# Esquema.net
KiCad netlist of a schematic drawn in EAGLE
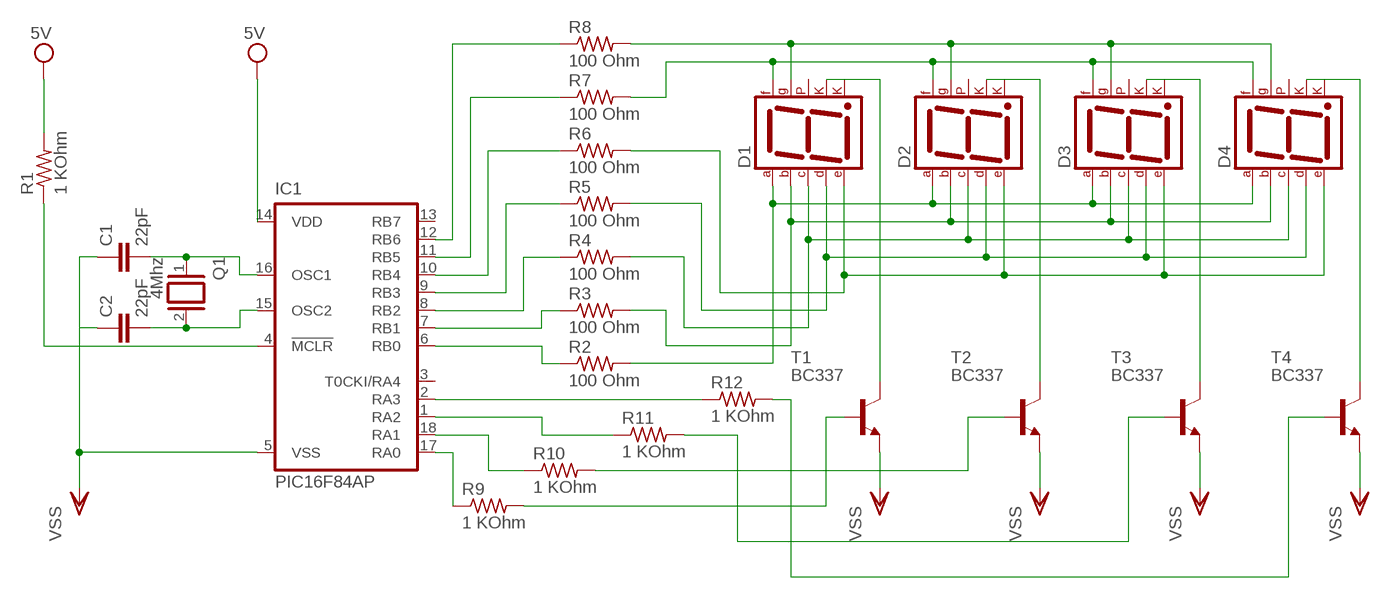
[diagram p0: schematic, sheet 1]

(export (version "E")
  (design (tool "Eeschema 10.0.6"))
  (components
    (comp (ref "C1")
      (value "22pF")
      (footprint "eagle-import:C2.5-4")
      (libsource (lib "eagle-import") (part "C2.5/4"))
    )
    (comp (ref "C2")
      (value "22pF")
      (footprint "eagle-import:C2.5-4")
      (libsource (lib "eagle-import") (part "C2.5/4"))
    )
    (comp (ref "D1")
      (value "7SEG-CK")
      (footprint "eagle-import:7SEG-13")
      (libsource (lib "eagle-import") (part "7SEG-CK"))
    )
    (comp (ref "D2")
      (value "7SEG-CK")
      (footprint "eagle-import:7SEG-13")
      (libsource (lib "eagle-import") (part "7SEG-CK"))
    )
    (comp (ref "D3")
      (value "7SEG-CK")
      (footprint "eagle-import:7SEG-13")
      (libsource (lib "eagle-import") (part "7SEG-CK"))
    )
    (comp (ref "D4")
      (value "7SEG-CK")
      (footprint "eagle-import:7SEG-13")
      (libsource (lib "eagle-import") (part "7SEG-CK"))
    )
    (comp (ref "IC1")
      (value "PIC16F84AP")
      (footprint "eagle-import:DIL18")
      (fields (field (name "MF") "MICROCHIP") (field (name "MPN") "PIC16F84A-04I/P"))
      (libsource (lib "eagle-import") (part "PIC16F8P4A"))
    )
    (comp (ref "Q1")
      (value "4Mhz")
      (footprint "eagle-import:Q")
      (libsource (lib "eagle-import") (part "XTAL"))
    )
    (comp (ref "R1")
      (value "1 KOhm")
      (footprint "eagle-import:0204_5")
      (libsource (lib "eagle-import") (part "R-US_0204/5"))
    )
    (comp (ref "R2")
      (value "100 Ohm")
      (footprint "eagle-import:0204_5")
      (libsource (lib "eagle-import") (part "R-US_0204/5"))
    )
    (comp (ref "R3")
      (value "100 Ohm")
      (footprint "eagle-import:0204_5")
      (libsource (lib "eagle-import") (part "R-US_0204/5"))
    )
    (comp (ref "R4")
      (value "100 Ohm")
      (footprint "eagle-import:0204_5")
      (libsource (lib "eagle-import") (part "R-US_0204/5"))
    )
    (comp (ref "R5")
      (value "100 Ohm")
      (footprint "eagle-import:0204_5")
      (libsource (lib "eagle-import") (part "R-US_0204/5"))
    )
    (comp (ref "R6")
      (value "100 Ohm")
      (footprint "eagle-import:0204_5")
      (libsource (lib "eagle-import") (part "R-US_0204/5"))
    )
    (comp (ref "R7")
      (value "100 Ohm")
      (footprint "eagle-import:0204_5")
      (libsource (lib "eagle-import") (part "R-US_0204/5"))
    )
    (comp (ref "R8")
      (value "100 Ohm")
      (footprint "eagle-import:0204_5")
      (libsource (lib "eagle-import") (part "R-US_0204/5"))
    )
    (comp (ref "R9")
      (value "1 KOhm")
      (footprint "eagle-import:0204_5")
      (libsource (lib "eagle-import") (part "R-US_0204/5"))
    )
    (comp (ref "R10")
      (value "1 KOhm")
      (footprint "eagle-import:0204_5")
      (libsource (lib "eagle-import") (part "R-US_0204/5"))
    )
    (comp (ref "R11")
      (value "1 KOhm")
      (footprint "eagle-import:0204_5")
      (libsource (lib "eagle-import") (part "R-US_0204/5"))
    )
    (comp (ref "R12")
      (value "1 KOhm")
      (footprint "eagle-import:0204_5")
      (libsource (lib "eagle-import") (part "R-US_0204/5"))
    )
    (comp (ref "T1")
      (value "BC337")
      (footprint "eagle-import:TO92")
      (libsource (lib "eagle-import") (part "BC337"))
    )
    (comp (ref "T2")
      (value "BC337")
      (footprint "eagle-import:TO92")
      (libsource (lib "eagle-import") (part "BC337"))
    )
    (comp (ref "T3")
      (value "BC337")
      (footprint "eagle-import:TO92")
      (libsource (lib "eagle-import") (part "BC337"))
    )
    (comp (ref "T4")
      (value "BC337")
      (footprint "eagle-import:TO92")
      (libsource (lib "eagle-import") (part "BC337"))
    )
  )
  (nets
    (net (code "1") (name "5V") (class "Default")
      (node (ref "IC1") (pin "14") (pinfunction "VDD_14") (pintype "power_in"))
      (node (ref "R1") (pin "2") (pinfunction "2_2") (pintype "passive"))
    )
    (net (code "2") (name "Net-(D1-A)") (class "Default")
      (node (ref "D1") (pin "7") (pinfunction "A_7") (pintype "passive"))
      (node (ref "D2") (pin "7") (pinfunction "A_7") (pintype "passive"))
      (node (ref "D3") (pin "7") (pinfunction "A_7") (pintype "passive"))
      (node (ref "D4") (pin "7") (pinfunction "A_7") (pintype "passive"))
      (node (ref "R2") (pin "2") (pinfunction "2_2") (pintype "passive"))
    )
    (net (code "3") (name "Net-(D1-B)") (class "Default")
      (node (ref "D1") (pin "6") (pinfunction "B_6") (pintype "passive"))
      (node (ref "D2") (pin "6") (pinfunction "B_6") (pintype "passive"))
      (node (ref "D3") (pin "6") (pinfunction "B_6") (pintype "passive"))
      (node (ref "D4") (pin "6") (pinfunction "B_6") (pintype "passive"))
      (node (ref "R3") (pin "2") (pinfunction "2_2") (pintype "passive"))
    )
    (net (code "4") (name "Net-(D1-C)") (class "Default")
      (node (ref "D1") (pin "4") (pinfunction "C_4") (pintype "passive"))
      (node (ref "D2") (pin "4") (pinfunction "C_4") (pintype "passive"))
      (node (ref "D3") (pin "4") (pinfunction "C_4") (pintype "passive"))
      (node (ref "D4") (pin "4") (pinfunction "C_4") (pintype "passive"))
      (node (ref "R4") (pin "2") (pinfunction "2_2") (pintype "passive"))
    )
    (net (code "5") (name "Net-(D1-CK1)") (class "Default")
      (node (ref "D1") (pin "3") (pinfunction "CK1_3") (pintype "passive"))
      (node (ref "D1") (pin "8") (pinfunction "CK2_8") (pintype "passive"))
      (node (ref "T1") (pin "3") (pinfunction "C_3") (pintype "passive"))
    )
    (net (code "6") (name "Net-(D1-D)") (class "Default")
      (node (ref "D1") (pin "2") (pinfunction "D_2") (pintype "passive"))
      (node (ref "D2") (pin "2") (pinfunction "D_2") (pintype "passive"))
      (node (ref "D3") (pin "2") (pinfunction "D_2") (pintype "passive"))
      (node (ref "D4") (pin "2") (pinfunction "D_2") (pintype "passive"))
      (node (ref "R5") (pin "2") (pinfunction "2_2") (pintype "passive"))
    )
    (net (code "7") (name "Net-(D1-E)") (class "Default")
      (node (ref "D1") (pin "1") (pinfunction "E_1") (pintype "passive"))
      (node (ref "D2") (pin "1") (pinfunction "E_1") (pintype "passive"))
      (node (ref "D3") (pin "1") (pinfunction "E_1") (pintype "passive"))
      (node (ref "D4") (pin "1") (pinfunction "E_1") (pintype "passive"))
      (node (ref "R6") (pin "2") (pinfunction "2_2") (pintype "passive"))
    )
    (net (code "8") (name "Net-(D1-F)") (class "Default")
      (node (ref "D1") (pin "9") (pinfunction "F_9") (pintype "passive"))
      (node (ref "D2") (pin "9") (pinfunction "F_9") (pintype "passive"))
      (node (ref "D3") (pin "9") (pinfunction "F_9") (pintype "passive"))
      (node (ref "D4") (pin "9") (pinfunction "F_9") (pintype "passive"))
      (node (ref "R7") (pin "2") (pinfunction "2_2") (pintype "passive"))
    )
    (net (code "9") (name "Net-(D1-G)") (class "Default")
      (node (ref "D1") (pin "10") (pinfunction "G_10") (pintype "passive"))
      (node (ref "D2") (pin "10") (pinfunction "G_10") (pintype "passive"))
      (node (ref "D3") (pin "10") (pinfunction "G_10") (pintype "passive"))
      (node (ref "D4") (pin "10") (pinfunction "G_10") (pintype "passive"))
      (node (ref "R8") (pin "2") (pinfunction "2_2") (pintype "passive"))
    )
    (net (code "10") (name "Net-(D2-CK1)") (class "Default")
      (node (ref "D2") (pin "3") (pinfunction "CK1_3") (pintype "passive"))
      (node (ref "D2") (pin "8") (pinfunction "CK2_8") (pintype "passive"))
      (node (ref "T2") (pin "3") (pinfunction "C_3") (pintype "passive"))
    )
    (net (code "11") (name "Net-(D3-CK1)") (class "Default")
      (node (ref "D3") (pin "3") (pinfunction "CK1_3") (pintype "passive"))
      (node (ref "D3") (pin "8") (pinfunction "CK2_8") (pintype "passive"))
      (node (ref "T3") (pin "3") (pinfunction "C_3") (pintype "passive"))
    )
    (net (code "12") (name "Net-(D4-CK1)") (class "Default")
      (node (ref "D4") (pin "3") (pinfunction "CK1_3") (pintype "passive"))
      (node (ref "D4") (pin "8") (pinfunction "CK2_8") (pintype "passive"))
      (node (ref "T4") (pin "3") (pinfunction "C_3") (pintype "passive"))
    )
    (net (code "13") (name "Net-(IC1-OSC1)") (class "Default")
      (node (ref "C1") (pin "2") (pinfunction "2_2") (pintype "passive"))
      (node (ref "IC1") (pin "16") (pinfunction "OSC1_16") (pintype "input"))
      (node (ref "Q1") (pin "1") (pinfunction "1_1") (pintype "passive"))
    )
    (net (code "14") (name "Net-(IC1-OSC2)") (class "Default")
      (node (ref "C2") (pin "2") (pinfunction "2_2") (pintype "passive"))
      (node (ref "IC1") (pin "15") (pinfunction "OSC2_15") (pintype "output"))
      (node (ref "Q1") (pin "2") (pinfunction "2_2") (pintype "passive"))
    )
    (net (code "15") (name "Net-(IC1-RA0)") (class "Default")
      (node (ref "IC1") (pin "17") (pinfunction "RA0_17") (pintype "bidirectional"))
      (node (ref "R9") (pin "1") (pinfunction "1_1") (pintype "passive"))
    )
    (net (code "16") (name "Net-(IC1-RA1)") (class "Default")
      (node (ref "IC1") (pin "18") (pinfunction "RA1_18") (pintype "bidirectional"))
      (node (ref "R10") (pin "1") (pinfunction "1_1") (pintype "passive"))
    )
    (net (code "17") (name "Net-(IC1-RA2)") (class "Default")
      (node (ref "IC1") (pin "1") (pinfunction "RA2_1") (pintype "bidirectional"))
      (node (ref "R11") (pin "1") (pinfunction "1_1") (pintype "passive"))
    )
    (net (code "18") (name "Net-(IC1-RA3)") (class "Default")
      (node (ref "IC1") (pin "2") (pinfunction "RA3_2") (pintype "bidirectional"))
      (node (ref "R12") (pin "1") (pinfunction "1_1") (pintype "passive"))
    )
    (net (code "19") (name "Net-(IC1-RB0)") (class "Default")
      (node (ref "IC1") (pin "6") (pinfunction "RB0_6") (pintype "bidirectional"))
      (node (ref "R2") (pin "1") (pinfunction "1_1") (pintype "passive"))
    )
    (net (code "20") (name "Net-(IC1-RB1)") (class "Default")
      (node (ref "IC1") (pin "7") (pinfunction "RB1_7") (pintype "bidirectional"))
      (node (ref "R3") (pin "1") (pinfunction "1_1") (pintype "passive"))
    )
    (net (code "21") (name "Net-(IC1-RB2)") (class "Default")
      (node (ref "IC1") (pin "8") (pinfunction "RB2_8") (pintype "bidirectional"))
      (node (ref "R4") (pin "1") (pinfunction "1_1") (pintype "passive"))
    )
    (net (code "22") (name "Net-(IC1-RB3)") (class "Default")
      (node (ref "IC1") (pin "9") (pinfunction "RB3_9") (pintype "bidirectional"))
      (node (ref "R5") (pin "1") (pinfunction "1_1") (pintype "passive"))
    )
    (net (code "23") (name "Net-(IC1-RB4)") (class "Default")
      (node (ref "IC1") (pin "10") (pinfunction "RB4_10") (pintype "bidirectional"))
      (node (ref "R6") (pin "1") (pinfunction "1_1") (pintype "passive"))
    )
    (net (code "24") (name "Net-(IC1-RB5)") (class "Default")
      (node (ref "IC1") (pin "11") (pinfunction "RB5_11") (pintype "bidirectional"))
      (node (ref "R7") (pin "1") (pinfunction "1_1") (pintype "passive"))
    )
    (net (code "25") (name "Net-(IC1-RB6)") (class "Default")
      (node (ref "IC1") (pin "12") (pinfunction "RB6_12") (pintype "bidirectional"))
      (node (ref "R8") (pin "1") (pinfunction "1_1") (pintype "passive"))
    )
    (net (code "26") (name "Net-(IC1-~{MCLR})") (class "Default")
      (node (ref "IC1") (pin "4") (pinfunction "~{MCLR}_4") (pintype "input"))
      (node (ref "R1") (pin "1") (pinfunction "1_1") (pintype "passive"))
    )
    (net (code "27") (name "Net-(T1-B)") (class "Default")
      (node (ref "R9") (pin "2") (pinfunction "2_2") (pintype "passive"))
      (node (ref "T1") (pin "2") (pinfunction "B_2") (pintype "passive"))
    )
    (net (code "28") (name "Net-(T2-B)") (class "Default")
      (node (ref "R10") (pin "2") (pinfunction "2_2") (pintype "passive"))
      (node (ref "T2") (pin "2") (pinfunction "B_2") (pintype "passive"))
    )
    (net (code "29") (name "Net-(T3-B)") (class "Default")
      (node (ref "R11") (pin "2") (pinfunction "2_2") (pintype "passive"))
      (node (ref "T3") (pin "2") (pinfunction "B_2") (pintype "passive"))
    )
    (net (code "30") (name "Net-(T4-B)") (class "Default")
      (node (ref "R12") (pin "2") (pinfunction "2_2") (pintype "passive"))
      (node (ref "T4") (pin "2") (pinfunction "B_2") (pintype "passive"))
    )
    (net (code "31") (name "VSS") (class "Default")
      (node (ref "C1") (pin "1") (pinfunction "1_1") (pintype "passive"))
      (node (ref "C2") (pin "1") (pinfunction "1_1") (pintype "passive"))
      (node (ref "IC1") (pin "5") (pinfunction "VSS_5") (pintype "power_in"))
      (node (ref "T1") (pin "1") (pinfunction "E_1") (pintype "passive"))
      (node (ref "T2") (pin "1") (pinfunction "E_1") (pintype "passive"))
      (node (ref "T3") (pin "1") (pinfunction "E_1") (pintype "passive"))
      (node (ref "T4") (pin "1") (pinfunction "E_1") (pintype "passive"))
    )
    (net (code "32") (name "unconnected-(D1-DP-Pad5)") (class "Default")
      (node (ref "D1") (pin "5") (pinfunction "DP_5") (pintype "passive"))
    )
    (net (code "33") (name "unconnected-(D2-DP-Pad5)") (class "Default")
      (node (ref "D2") (pin "5") (pinfunction "DP_5") (pintype "passive"))
    )
    (net (code "34") (name "unconnected-(D3-DP-Pad5)") (class "Default")
      (node (ref "D3") (pin "5") (pinfunction "DP_5") (pintype "passive"))
    )
    (net (code "35") (name "unconnected-(D4-DP-Pad5)") (class "Default")
      (node (ref "D4") (pin "5") (pinfunction "DP_5") (pintype "passive"))
    )
    (net (code "36") (name "unconnected-(IC1-RB7-Pad13)") (class "Default")
      (node (ref "IC1") (pin "13") (pinfunction "RB7_13") (pintype "bidirectional"))
    )
    (net (code "37") (name "unconnected-(IC1-T0CKI{slash}RA4-Pad3)") (class "Default")
      (node (ref "IC1") (pin "3") (pinfunction "T0CKI/RA4_3") (pintype "bidirectional"))
    )
  )
)
